# box_opener.net
KiCad netlist of a schematic drawn in EAGLE
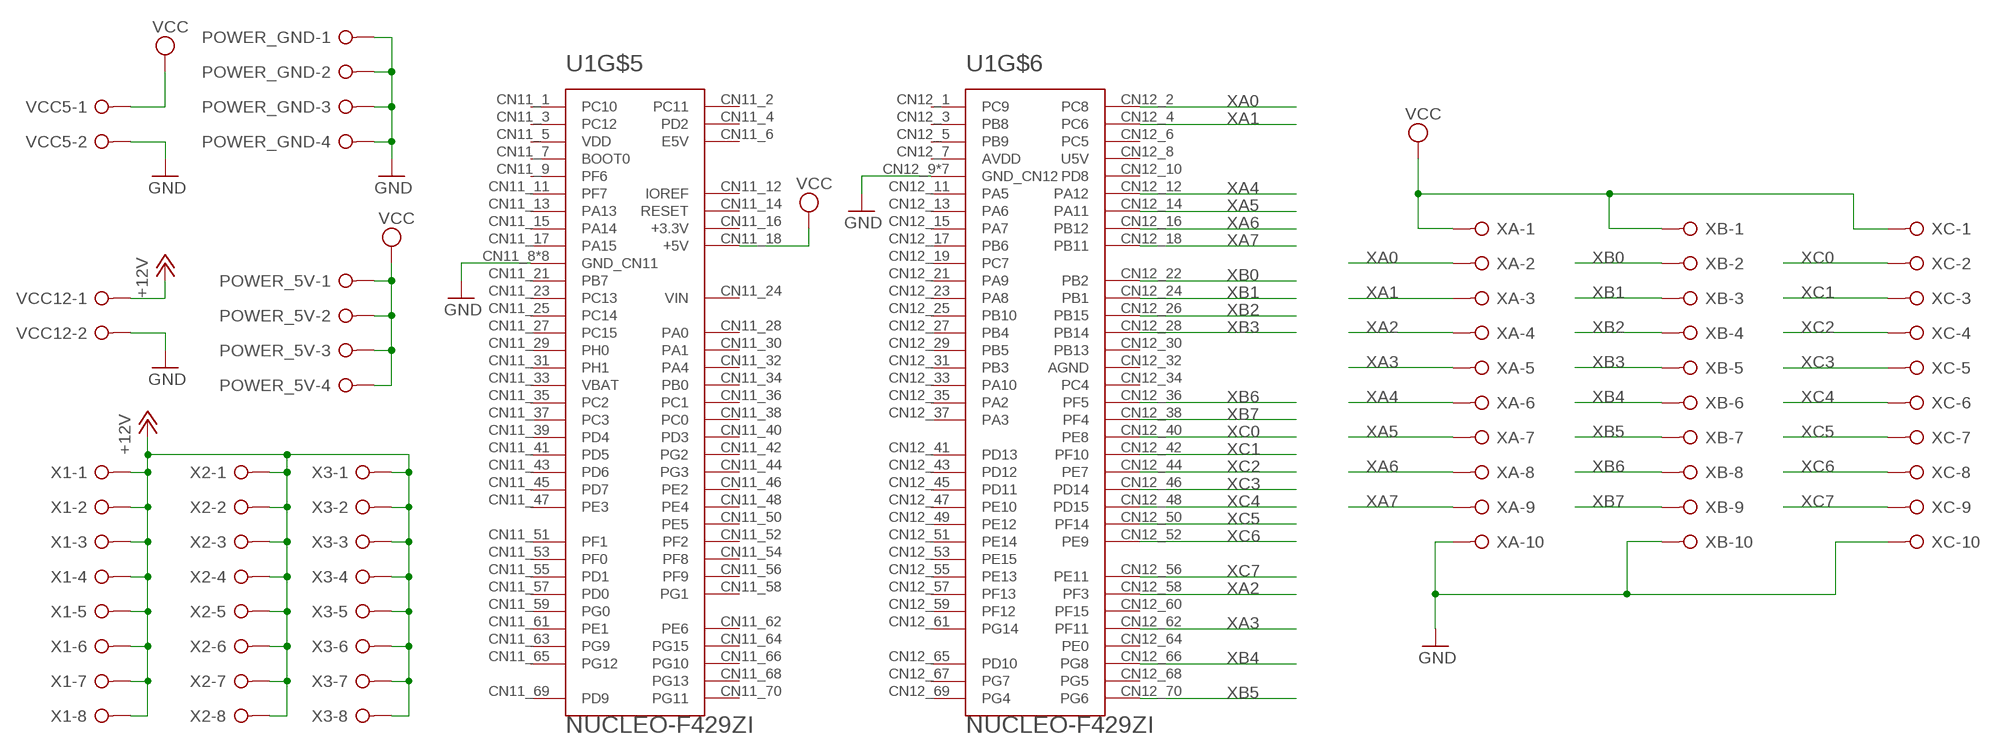
[diagram p0: schematic, sheet 1]

(export (version "E")
  (design (tool "Eeschema 10.0.6"))
  (components
    (comp (ref "POWER_5V")
      (value "W237-04P")
      (footprint "eagle-import:W237-4P")
      (libsource (lib "eagle-import") (part "W237-04P"))
    )
    (comp (ref "POWER_GND")
      (value "W237-04P")
      (footprint "eagle-import:W237-4P")
      (libsource (lib "eagle-import") (part "W237-04P"))
    )
    (comp (ref "U1")
      (value "NUCLEO-F429ZI")
      (footprint "eagle-import:MODULE_NUCLEO-F429ZI")
      (fields (field (name "MF") "STMicroelectronics"))
      (libsource (lib "eagle-import") (part "NUCLEO-F429ZI"))
    )
    (comp (ref "VCC5")
      (value "W237-02P")
      (footprint "eagle-import:W237-132")
      (libsource (lib "eagle-import") (part "W237-02P"))
    )
    (comp (ref "VCC12")
      (value "W237-02P")
      (footprint "eagle-import:W237-132")
      (libsource (lib "eagle-import") (part "W237-02P"))
    )
    (comp (ref "X1")
      (value "W237-08P")
      (footprint "eagle-import:W237-8P")
      (libsource (lib "eagle-import") (part "W237-08P"))
    )
    (comp (ref "X2")
      (value "W237-08P")
      (footprint "eagle-import:W237-8P")
      (libsource (lib "eagle-import") (part "W237-08P"))
    )
    (comp (ref "X3")
      (value "W237-08P")
      (footprint "eagle-import:W237-8P")
      (libsource (lib "eagle-import") (part "W237-08P"))
    )
    (comp (ref "XA")
      (value "W237-10P")
      (footprint "eagle-import:W237-10P")
      (libsource (lib "eagle-import") (part "W237-10P"))
    )
    (comp (ref "XB")
      (value "W237-10P")
      (footprint "eagle-import:W237-10P")
      (libsource (lib "eagle-import") (part "W237-10P"))
    )
    (comp (ref "XC")
      (value "W237-10P")
      (footprint "eagle-import:W237-10P")
      (libsource (lib "eagle-import") (part "W237-10P"))
    )
  )
  (nets
    (net (code "1") (name "+12V") (class "Default")
      (node (ref "VCC12") (pin "1") (pinfunction "KL_1") (pintype "passive"))
      (node (ref "X1") (pin "1") (pinfunction "KL_1") (pintype "passive"))
      (node (ref "X1") (pin "2") (pinfunction "KL_2") (pintype "passive"))
      (node (ref "X1") (pin "3") (pinfunction "KL_3") (pintype "passive"))
      (node (ref "X1") (pin "4") (pinfunction "KL_4") (pintype "passive"))
      (node (ref "X1") (pin "5") (pinfunction "KL_5") (pintype "passive"))
      (node (ref "X1") (pin "6") (pinfunction "KL_6") (pintype "passive"))
      (node (ref "X1") (pin "7") (pinfunction "KL_7") (pintype "passive"))
      (node (ref "X1") (pin "8") (pinfunction "KL_8") (pintype "passive"))
      (node (ref "X2") (pin "1") (pinfunction "KL_1") (pintype "passive"))
      (node (ref "X2") (pin "2") (pinfunction "KL_2") (pintype "passive"))
      (node (ref "X2") (pin "3") (pinfunction "KL_3") (pintype "passive"))
      (node (ref "X2") (pin "4") (pinfunction "KL_4") (pintype "passive"))
      (node (ref "X2") (pin "5") (pinfunction "KL_5") (pintype "passive"))
      (node (ref "X2") (pin "6") (pinfunction "KL_6") (pintype "passive"))
      (node (ref "X2") (pin "7") (pinfunction "KL_7") (pintype "passive"))
      (node (ref "X2") (pin "8") (pinfunction "KL_8") (pintype "passive"))
      (node (ref "X3") (pin "1") (pinfunction "KL_1") (pintype "passive"))
      (node (ref "X3") (pin "2") (pinfunction "KL_2") (pintype "passive"))
      (node (ref "X3") (pin "3") (pinfunction "KL_3") (pintype "passive"))
      (node (ref "X3") (pin "4") (pinfunction "KL_4") (pintype "passive"))
      (node (ref "X3") (pin "5") (pinfunction "KL_5") (pintype "passive"))
      (node (ref "X3") (pin "6") (pinfunction "KL_6") (pintype "passive"))
      (node (ref "X3") (pin "7") (pinfunction "KL_7") (pintype "passive"))
      (node (ref "X3") (pin "8") (pinfunction "KL_8") (pintype "passive"))
    )
    (net (code "2") (name "/XA0") (class "Default")
      (node (ref "U1") (pin "CN12_2") (pinfunction "PC8_CN12_2") (pintype "passive"))
      (node (ref "XA") (pin "2") (pinfunction "KL_2") (pintype "passive"))
    )
    (net (code "3") (name "/XA1") (class "Default")
      (node (ref "U1") (pin "CN12_4") (pinfunction "PC6_CN12_4") (pintype "passive"))
      (node (ref "XA") (pin "3") (pinfunction "KL_3") (pintype "passive"))
    )
    (net (code "4") (name "/XA2") (class "Default")
      (node (ref "U1") (pin "CN12_58") (pinfunction "PF3_CN12_58") (pintype "passive"))
      (node (ref "XA") (pin "4") (pinfunction "KL_4") (pintype "passive"))
    )
    (net (code "5") (name "/XA3") (class "Default")
      (node (ref "U1") (pin "CN12_62") (pinfunction "PF11_CN12_62") (pintype "passive"))
      (node (ref "XA") (pin "5") (pinfunction "KL_5") (pintype "passive"))
    )
    (net (code "6") (name "/XA4") (class "Default")
      (node (ref "U1") (pin "CN12_12") (pinfunction "PA12_CN12_12") (pintype "passive"))
      (node (ref "XA") (pin "6") (pinfunction "KL_6") (pintype "passive"))
    )
    (net (code "7") (name "/XA5") (class "Default")
      (node (ref "U1") (pin "CN12_14") (pinfunction "PA11_CN12_14") (pintype "passive"))
      (node (ref "XA") (pin "7") (pinfunction "KL_7") (pintype "passive"))
    )
    (net (code "8") (name "/XA6") (class "Default")
      (node (ref "U1") (pin "CN12_16") (pinfunction "PB12_CN12_16") (pintype "passive"))
      (node (ref "XA") (pin "8") (pinfunction "KL_8") (pintype "passive"))
    )
    (net (code "9") (name "/XA7") (class "Default")
      (node (ref "U1") (pin "CN12_18") (pinfunction "PB11_CN12_18") (pintype "passive"))
      (node (ref "XA") (pin "9") (pinfunction "KL_9") (pintype "passive"))
    )
    (net (code "10") (name "/XB0") (class "Default")
      (node (ref "U1") (pin "CN12_22") (pinfunction "PB2_CN12_22") (pintype "passive"))
      (node (ref "XB") (pin "2") (pinfunction "KL_2") (pintype "passive"))
    )
    (net (code "11") (name "/XB1") (class "Default")
      (node (ref "U1") (pin "CN12_24") (pinfunction "PB1_CN12_24") (pintype "passive"))
      (node (ref "XB") (pin "3") (pinfunction "KL_3") (pintype "passive"))
    )
    (net (code "12") (name "/XB2") (class "Default")
      (node (ref "U1") (pin "CN12_26") (pinfunction "PB15_CN12_26") (pintype "passive"))
      (node (ref "XB") (pin "4") (pinfunction "KL_4") (pintype "passive"))
    )
    (net (code "13") (name "/XB3") (class "Default")
      (node (ref "U1") (pin "CN12_28") (pinfunction "PB14_CN12_28") (pintype "passive"))
      (node (ref "XB") (pin "5") (pinfunction "KL_5") (pintype "passive"))
    )
    (net (code "14") (name "/XB4") (class "Default")
      (node (ref "U1") (pin "CN12_66") (pinfunction "PG8_CN12_66") (pintype "passive"))
      (node (ref "XB") (pin "6") (pinfunction "KL_6") (pintype "passive"))
    )
    (net (code "15") (name "/XB5") (class "Default")
      (node (ref "U1") (pin "CN12_70") (pinfunction "PG6_CN12_70") (pintype "passive"))
      (node (ref "XB") (pin "7") (pinfunction "KL_7") (pintype "passive"))
    )
    (net (code "16") (name "/XB6") (class "Default")
      (node (ref "U1") (pin "CN12_36") (pinfunction "PF5_CN12_36") (pintype "passive"))
      (node (ref "XB") (pin "8") (pinfunction "KL_8") (pintype "passive"))
    )
    (net (code "17") (name "/XB7") (class "Default")
      (node (ref "U1") (pin "CN12_38") (pinfunction "PF4_CN12_38") (pintype "passive"))
      (node (ref "XB") (pin "9") (pinfunction "KL_9") (pintype "passive"))
    )
    (net (code "18") (name "/XC0") (class "Default")
      (node (ref "U1") (pin "CN12_40") (pinfunction "PE8_CN12_40") (pintype "passive"))
      (node (ref "XC") (pin "2") (pinfunction "KL_2") (pintype "passive"))
    )
    (net (code "19") (name "/XC1") (class "Default")
      (node (ref "U1") (pin "CN12_42") (pinfunction "PF10_CN12_42") (pintype "passive"))
      (node (ref "XC") (pin "3") (pinfunction "KL_3") (pintype "passive"))
    )
    (net (code "20") (name "/XC2") (class "Default")
      (node (ref "U1") (pin "CN12_44") (pinfunction "PE7_CN12_44") (pintype "passive"))
      (node (ref "XC") (pin "4") (pinfunction "KL_4") (pintype "passive"))
    )
    (net (code "21") (name "/XC3") (class "Default")
      (node (ref "U1") (pin "CN12_46") (pinfunction "PD14_CN12_46") (pintype "passive"))
      (node (ref "XC") (pin "5") (pinfunction "KL_5") (pintype "passive"))
    )
    (net (code "22") (name "/XC4") (class "Default")
      (node (ref "U1") (pin "CN12_48") (pinfunction "PD15_CN12_48") (pintype "passive"))
      (node (ref "XC") (pin "6") (pinfunction "KL_6") (pintype "passive"))
    )
    (net (code "23") (name "/XC5") (class "Default")
      (node (ref "U1") (pin "CN12_50") (pinfunction "PF14_CN12_50") (pintype "passive"))
      (node (ref "XC") (pin "7") (pinfunction "KL_7") (pintype "passive"))
    )
    (net (code "24") (name "/XC6") (class "Default")
      (node (ref "U1") (pin "CN12_52") (pinfunction "PE9_CN12_52") (pintype "passive"))
      (node (ref "XC") (pin "8") (pinfunction "KL_8") (pintype "passive"))
    )
    (net (code "25") (name "/XC7") (class "Default")
      (node (ref "U1") (pin "CN12_56") (pinfunction "PE11_CN12_56") (pintype "passive"))
      (node (ref "XC") (pin "9") (pinfunction "KL_9") (pintype "passive"))
    )
    (net (code "26") (name "GND") (class "Default")
      (node (ref "POWER_GND") (pin "1") (pinfunction "KL_1") (pintype "passive"))
      (node (ref "POWER_GND") (pin "2") (pinfunction "KL_2") (pintype "passive"))
      (node (ref "POWER_GND") (pin "3") (pinfunction "KL_3") (pintype "passive"))
      (node (ref "POWER_GND") (pin "4") (pinfunction "KL_4") (pintype "passive"))
      (node (ref "U1") (pin "CN11_19") (pinfunction "GND_CN11_CN11_19") (pintype "passive"))
      (node (ref "U1") (pin "CN11_20") (pinfunction "GND_CN11_CN11_20") (pintype "passive"))
      (node (ref "U1") (pin "CN11_22") (pinfunction "GND_CN11_CN11_22") (pintype "passive"))
      (node (ref "U1") (pin "CN11_49") (pinfunction "GND_CN11_CN11_49") (pintype "passive"))
      (node (ref "U1") (pin "CN11_60") (pinfunction "GND_CN11_CN11_60") (pintype "passive"))
      (node (ref "U1") (pin "CN11_71") (pinfunction "GND_CN11_CN11_71") (pintype "passive"))
      (node (ref "U1") (pin "CN11_72") (pinfunction "GND_CN11_CN11_72") (pintype "passive"))
      (node (ref "U1") (pin "CN11_8") (pinfunction "GND_CN11_CN11_8") (pintype "passive"))
      (node (ref "U1") (pin "CN12_20") (pinfunction "GND_CN12_CN12_20") (pintype "passive"))
      (node (ref "U1") (pin "CN12_39") (pinfunction "GND_CN12_CN12_39") (pintype "passive"))
      (node (ref "U1") (pin "CN12_54") (pinfunction "GND_CN12_CN12_54") (pintype "passive"))
      (node (ref "U1") (pin "CN12_63") (pinfunction "GND_CN12_CN12_63") (pintype "passive"))
      (node (ref "U1") (pin "CN12_71") (pinfunction "GND_CN12_CN12_71") (pintype "passive"))
      (node (ref "U1") (pin "CN12_72") (pinfunction "GND_CN12_CN12_72") (pintype "passive"))
      (node (ref "U1") (pin "CN12_9") (pinfunction "GND_CN12_CN12_9") (pintype "passive"))
      (node (ref "VCC12") (pin "2") (pinfunction "KL_2") (pintype "passive"))
      (node (ref "VCC5") (pin "2") (pinfunction "KL_2") (pintype "passive"))
      (node (ref "XA") (pin "10") (pinfunction "KL_10") (pintype "passive"))
      (node (ref "XB") (pin "10") (pinfunction "KL_10") (pintype "passive"))
      (node (ref "XC") (pin "10") (pinfunction "KL_10") (pintype "passive"))
    )
    (net (code "27") (name "VCC") (class "Default")
      (node (ref "POWER_5V") (pin "1") (pinfunction "KL_1") (pintype "passive"))
      (node (ref "POWER_5V") (pin "2") (pinfunction "KL_2") (pintype "passive"))
      (node (ref "POWER_5V") (pin "3") (pinfunction "KL_3") (pintype "passive"))
      (node (ref "POWER_5V") (pin "4") (pinfunction "KL_4") (pintype "passive"))
      (node (ref "U1") (pin "CN11_18") (pinfunction "+5V_CN11_18") (pintype "passive"))
      (node (ref "VCC5") (pin "1") (pinfunction "KL_1") (pintype "passive"))
      (node (ref "XA") (pin "1") (pinfunction "KL_1") (pintype "passive"))
      (node (ref "XB") (pin "1") (pinfunction "KL_1") (pintype "passive"))
      (node (ref "XC") (pin "1") (pinfunction "KL_1") (pintype "passive"))
    )
    (net (code "28") (name "unconnected-(U1E-+3.3V-PadCN11_16)") (class "Default")
      (node (ref "U1") (pin "CN11_16") (pinfunction "+3.3V_CN11_16") (pintype "passive"))
    )
    (net (code "29") (name "unconnected-(U1E-BOOT0-PadCN11_7)") (class "Default")
      (node (ref "U1") (pin "CN11_7") (pinfunction "BOOT0_CN11_7") (pintype "passive"))
    )
    (net (code "30") (name "unconnected-(U1E-E5V-PadCN11_6)") (class "Default")
      (node (ref "U1") (pin "CN11_6") (pinfunction "E5V_CN11_6") (pintype "passive"))
    )
    (net (code "31") (name "unconnected-(U1E-IOREF-PadCN11_12)") (class "Default")
      (node (ref "U1") (pin "CN11_12") (pinfunction "IOREF_CN11_12") (pintype "passive"))
    )
    (net (code "32") (name "unconnected-(U1E-PA0-PadCN11_28)") (class "Default")
      (node (ref "U1") (pin "CN11_28") (pinfunction "PA0_CN11_28") (pintype "passive"))
    )
    (net (code "33") (name "unconnected-(U1E-PA1-PadCN11_30)") (class "Default")
      (node (ref "U1") (pin "CN11_30") (pinfunction "PA1_CN11_30") (pintype "passive"))
    )
    (net (code "34") (name "unconnected-(U1E-PA4-PadCN11_32)") (class "Default")
      (node (ref "U1") (pin "CN11_32") (pinfunction "PA4_CN11_32") (pintype "passive"))
    )
    (net (code "35") (name "unconnected-(U1E-PA13-PadCN11_13)") (class "Default")
      (node (ref "U1") (pin "CN11_13") (pinfunction "PA13_CN11_13") (pintype "passive"))
    )
    (net (code "36") (name "unconnected-(U1E-PA14-PadCN11_15)") (class "Default")
      (node (ref "U1") (pin "CN11_15") (pinfunction "PA14_CN11_15") (pintype "passive"))
    )
    (net (code "37") (name "unconnected-(U1E-PA15-PadCN11_17)") (class "Default")
      (node (ref "U1") (pin "CN11_17") (pinfunction "PA15_CN11_17") (pintype "passive"))
    )
    (net (code "38") (name "unconnected-(U1E-PB0-PadCN11_34)") (class "Default")
      (node (ref "U1") (pin "CN11_34") (pinfunction "PB0_CN11_34") (pintype "passive"))
    )
    (net (code "39") (name "unconnected-(U1E-PB7-PadCN11_21)") (class "Default")
      (node (ref "U1") (pin "CN11_21") (pinfunction "PB7_CN11_21") (pintype "passive"))
    )
    (net (code "40") (name "unconnected-(U1E-PC0-PadCN11_38)") (class "Default")
      (node (ref "U1") (pin "CN11_38") (pinfunction "PC0_CN11_38") (pintype "passive"))
    )
    (net (code "41") (name "unconnected-(U1E-PC1-PadCN11_36)") (class "Default")
      (node (ref "U1") (pin "CN11_36") (pinfunction "PC1_CN11_36") (pintype "passive"))
    )
    (net (code "42") (name "unconnected-(U1E-PC2-PadCN11_35)") (class "Default")
      (node (ref "U1") (pin "CN11_35") (pinfunction "PC2_CN11_35") (pintype "passive"))
    )
    (net (code "43") (name "unconnected-(U1E-PC3-PadCN11_37)") (class "Default")
      (node (ref "U1") (pin "CN11_37") (pinfunction "PC3_CN11_37") (pintype "passive"))
    )
    (net (code "44") (name "unconnected-(U1E-PC10-PadCN11_1)") (class "Default")
      (node (ref "U1") (pin "CN11_1") (pinfunction "PC10_CN11_1") (pintype "passive"))
    )
    (net (code "45") (name "unconnected-(U1E-PC11-PadCN11_2)") (class "Default")
      (node (ref "U1") (pin "CN11_2") (pinfunction "PC11_CN11_2") (pintype "passive"))
    )
    (net (code "46") (name "unconnected-(U1E-PC12-PadCN11_3)") (class "Default")
      (node (ref "U1") (pin "CN11_3") (pinfunction "PC12_CN11_3") (pintype "passive"))
    )
    (net (code "47") (name "unconnected-(U1E-PC13-PadCN11_23)") (class "Default")
      (node (ref "U1") (pin "CN11_23") (pinfunction "PC13_CN11_23") (pintype "passive"))
    )
    (net (code "48") (name "unconnected-(U1E-PC14-PadCN11_25)") (class "Default")
      (node (ref "U1") (pin "CN11_25") (pinfunction "PC14_CN11_25") (pintype "passive"))
    )
    (net (code "49") (name "unconnected-(U1E-PC15-PadCN11_27)") (class "Default")
      (node (ref "U1") (pin "CN11_27") (pinfunction "PC15_CN11_27") (pintype "passive"))
    )
    (net (code "50") (name "unconnected-(U1E-PD0-PadCN11_57)") (class "Default")
      (node (ref "U1") (pin "CN11_57") (pinfunction "PD0_CN11_57") (pintype "passive"))
    )
    (net (code "51") (name "unconnected-(U1E-PD1-PadCN11_55)") (class "Default")
      (node (ref "U1") (pin "CN11_55") (pinfunction "PD1_CN11_55") (pintype "passive"))
    )
    (net (code "52") (name "unconnected-(U1E-PD2-PadCN11_4)") (class "Default")
      (node (ref "U1") (pin "CN11_4") (pinfunction "PD2_CN11_4") (pintype "passive"))
    )
    (net (code "53") (name "unconnected-(U1E-PD3-PadCN11_40)") (class "Default")
      (node (ref "U1") (pin "CN11_40") (pinfunction "PD3_CN11_40") (pintype "passive"))
    )
    (net (code "54") (name "unconnected-(U1E-PD4-PadCN11_39)") (class "Default")
      (node (ref "U1") (pin "CN11_39") (pinfunction "PD4_CN11_39") (pintype "passive"))
    )
    (net (code "55") (name "unconnected-(U1E-PD5-PadCN11_41)") (class "Default")
      (node (ref "U1") (pin "CN11_41") (pinfunction "PD5_CN11_41") (pintype "passive"))
    )
    (net (code "56") (name "unconnected-(U1E-PD6-PadCN11_43)") (class "Default")
      (node (ref "U1") (pin "CN11_43") (pinfunction "PD6_CN11_43") (pintype "passive"))
    )
    (net (code "57") (name "unconnected-(U1E-PD7-PadCN11_45)") (class "Default")
      (node (ref "U1") (pin "CN11_45") (pinfunction "PD7_CN11_45") (pintype "passive"))
    )
    (net (code "58") (name "unconnected-(U1E-PD9-PadCN11_69)") (class "Default")
      (node (ref "U1") (pin "CN11_69") (pinfunction "PD9_CN11_69") (pintype "passive"))
    )
    (net (code "59") (name "unconnected-(U1E-PE1-PadCN11_61)") (class "Default")
      (node (ref "U1") (pin "CN11_61") (pinfunction "PE1_CN11_61") (pintype "passive"))
    )
    (net (code "60") (name "unconnected-(U1E-PE2-PadCN11_46)") (class "Default")
      (node (ref "U1") (pin "CN11_46") (pinfunction "PE2_CN11_46") (pintype "passive"))
    )
    (net (code "61") (name "unconnected-(U1E-PE3-PadCN11_47)") (class "Default")
      (node (ref "U1") (pin "CN11_47") (pinfunction "PE3_CN11_47") (pintype "passive"))
    )
    (net (code "62") (name "unconnected-(U1E-PE4-PadCN11_48)") (class "Default")
      (node (ref "U1") (pin "CN11_48") (pinfunction "PE4_CN11_48") (pintype "passive"))
    )
    (net (code "63") (name "unconnected-(U1E-PE5-PadCN11_50)") (class "Default")
      (node (ref "U1") (pin "CN11_50") (pinfunction "PE5_CN11_50") (pintype "passive"))
    )
    (net (code "64") (name "unconnected-(U1E-PE6-PadCN11_62)") (class "Default")
      (node (ref "U1") (pin "CN11_62") (pinfunction "PE6_CN11_62") (pintype "passive"))
    )
    (net (code "65") (name "unconnected-(U1E-PF0-PadCN11_53)") (class "Default")
      (node (ref "U1") (pin "CN11_53") (pinfunction "PF0_CN11_53") (pintype "passive"))
    )
    (net (code "66") (name "unconnected-(U1E-PF1-PadCN11_51)") (class "Default")
      (node (ref "U1") (pin "CN11_51") (pinfunction "PF1_CN11_51") (pintype "passive"))
    )
    (net (code "67") (name "unconnected-(U1E-PF2-PadCN11_52)") (class "Default")
      (node (ref "U1") (pin "CN11_52") (pinfunction "PF2_CN11_52") (pintype "passive"))
    )
    (net (code "68") (name "unconnected-(U1E-PF6-PadCN11_9)") (class "Default")
      (node (ref "U1") (pin "CN11_9") (pinfunction "PF6_CN11_9") (pintype "passive"))
    )
    (net (code "69") (name "unconnected-(U1E-PF7-PadCN11_11)") (class "Default")
      (node (ref "U1") (pin "CN11_11") (pinfunction "PF7_CN11_11") (pintype "passive"))
    )
    (net (code "70") (name "unconnected-(U1E-PF8-PadCN11_54)") (class "Default")
      (node (ref "U1") (pin "CN11_54") (pinfunction "PF8_CN11_54") (pintype "passive"))
    )
    (net (code "71") (name "unconnected-(U1E-PF9-PadCN11_56)") (class "Default")
      (node (ref "U1") (pin "CN11_56") (pinfunction "PF9_CN11_56") (pintype "passive"))
    )
    (net (code "72") (name "unconnected-(U1E-PG0-PadCN11_59)") (class "Default")
      (node (ref "U1") (pin "CN11_59") (pinfunction "PG0_CN11_59") (pintype "passive"))
    )
    (net (code "73") (name "unconnected-(U1E-PG1-PadCN11_58)") (class "Default")
      (node (ref "U1") (pin "CN11_58") (pinfunction "PG1_CN11_58") (pintype "passive"))
    )
    (net (code "74") (name "unconnected-(U1E-PG2-PadCN11_42)") (class "Default")
      (node (ref "U1") (pin "CN11_42") (pinfunction "PG2_CN11_42") (pintype "passive"))
    )
    (net (code "75") (name "unconnected-(U1E-PG3-PadCN11_44)") (class "Default")
      (node (ref "U1") (pin "CN11_44") (pinfunction "PG3_CN11_44") (pintype "passive"))
    )
    (net (code "76") (name "unconnected-(U1E-PG9-PadCN11_63)") (class "Default")
      (node (ref "U1") (pin "CN11_63") (pinfunction "PG9_CN11_63") (pintype "passive"))
    )
    (net (code "77") (name "unconnected-(U1E-PG10-PadCN11_66)") (class "Default")
      (node (ref "U1") (pin "CN11_66") (pinfunction "PG10_CN11_66") (pintype "passive"))
    )
    (net (code "78") (name "unconnected-(U1E-PG11-PadCN11_70)") (class "Default")
      (node (ref "U1") (pin "CN11_70") (pinfunction "PG11_CN11_70") (pintype "passive"))
    )
    (net (code "79") (name "unconnected-(U1E-PG12-PadCN11_65)") (class "Default")
      (node (ref "U1") (pin "CN11_65") (pinfunction "PG12_CN11_65") (pintype "passive"))
    )
    (net (code "80") (name "unconnected-(U1E-PG13-PadCN11_68)") (class "Default")
      (node (ref "U1") (pin "CN11_68") (pinfunction "PG13_CN11_68") (pintype "passive"))
    )
    (net (code "81") (name "unconnected-(U1E-PG15-PadCN11_64)") (class "Default")
      (node (ref "U1") (pin "CN11_64") (pinfunction "PG15_CN11_64") (pintype "passive"))
    )
    (net (code "82") (name "unconnected-(U1E-PH0-PadCN11_29)") (class "Default")
      (node (ref "U1") (pin "CN11_29") (pinfunction "PH0_CN11_29") (pintype "passive"))
    )
    (net (code "83") (name "unconnected-(U1E-PH1-PadCN11_31)") (class "Default")
      (node (ref "U1") (pin "CN11_31") (pinfunction "PH1_CN11_31") (pintype "passive"))
    )
    (net (code "84") (name "unconnected-(U1E-RESET-PadCN11_14)") (class "Default")
      (node (ref "U1") (pin "CN11_14") (pinfunction "RESET_CN11_14") (pintype "passive"))
    )
    (net (code "85") (name "unconnected-(U1E-VBAT-PadCN11_33)") (class "Default")
      (node (ref "U1") (pin "CN11_33") (pinfunction "VBAT_CN11_33") (pintype "passive"))
    )
    (net (code "86") (name "unconnected-(U1E-VDD-PadCN11_5)") (class "Default")
      (node (ref "U1") (pin "CN11_5") (pinfunction "VDD_CN11_5") (pintype "passive"))
    )
    (net (code "87") (name "unconnected-(U1E-VIN-PadCN11_24)") (class "Default")
      (node (ref "U1") (pin "CN11_24") (pinfunction "VIN_CN11_24") (pintype "passive"))
    )
    (net (code "88") (name "unconnected-(U1F-AGND-PadCN12_32)") (class "Default")
      (node (ref "U1") (pin "CN12_32") (pinfunction "AGND_CN12_32") (pintype "passive"))
    )
    (net (code "89") (name "unconnected-(U1F-AVDD-PadCN12_7)") (class "Default")
      (node (ref "U1") (pin "CN12_7") (pinfunction "AVDD_CN12_7") (pintype "passive"))
    )
    (net (code "90") (name "unconnected-(U1F-PA2-PadCN12_35)") (class "Default")
      (node (ref "U1") (pin "CN12_35") (pinfunction "PA2_CN12_35") (pintype "passive"))
    )
    (net (code "91") (name "unconnected-(U1F-PA3-PadCN12_37)") (class "Default")
      (node (ref "U1") (pin "CN12_37") (pinfunction "PA3_CN12_37") (pintype "passive"))
    )
    (net (code "92") (name "unconnected-(U1F-PA5-PadCN12_11)") (class "Default")
      (node (ref "U1") (pin "CN12_11") (pinfunction "PA5_CN12_11") (pintype "passive"))
    )
    (net (code "93") (name "unconnected-(U1F-PA6-PadCN12_13)") (class "Default")
      (node (ref "U1") (pin "CN12_13") (pinfunction "PA6_CN12_13") (pintype "passive"))
    )
    (net (code "94") (name "unconnected-(U1F-PA7-PadCN12_15)") (class "Default")
      (node (ref "U1") (pin "CN12_15") (pinfunction "PA7_CN12_15") (pintype "passive"))
    )
    (net (code "95") (name "unconnected-(U1F-PA8-PadCN12_23)") (class "Default")
      (node (ref "U1") (pin "CN12_23") (pinfunction "PA8_CN12_23") (pintype "passive"))
    )
    (net (code "96") (name "unconnected-(U1F-PA9-PadCN12_21)") (class "Default")
      (node (ref "U1") (pin "CN12_21") (pinfunction "PA9_CN12_21") (pintype "passive"))
    )
    (net (code "97") (name "unconnected-(U1F-PA10-PadCN12_33)") (class "Default")
      (node (ref "U1") (pin "CN12_33") (pinfunction "PA10_CN12_33") (pintype "passive"))
    )
    (net (code "98") (name "unconnected-(U1F-PB3-PadCN12_31)") (class "Default")
      (node (ref "U1") (pin "CN12_31") (pinfunction "PB3_CN12_31") (pintype "passive"))
    )
    (net (code "99") (name "unconnected-(U1F-PB4-PadCN12_27)") (class "Default")
      (node (ref "U1") (pin "CN12_27") (pinfunction "PB4_CN12_27") (pintype "passive"))
    )
    (net (code "100") (name "unconnected-(U1F-PB5-PadCN12_29)") (class "Default")
      (node (ref "U1") (pin "CN12_29") (pinfunction "PB5_CN12_29") (pintype "passive"))
    )
    (net (code "101") (name "unconnected-(U1F-PB6-PadCN12_17)") (class "Default")
      (node (ref "U1") (pin "CN12_17") (pinfunction "PB6_CN12_17") (pintype "passive"))
    )
    (net (code "102") (name "unconnected-(U1F-PB8-PadCN12_3)") (class "Default")
      (node (ref "U1") (pin "CN12_3") (pinfunction "PB8_CN12_3") (pintype "passive"))
    )
    (net (code "103") (name "unconnected-(U1F-PB9-PadCN12_5)") (class "Default")
      (node (ref "U1") (pin "CN12_5") (pinfunction "PB9_CN12_5") (pintype "passive"))
    )
    (net (code "104") (name "unconnected-(U1F-PB10-PadCN12_25)") (class "Default")
      (node (ref "U1") (pin "CN12_25") (pinfunction "PB10_CN12_25") (pintype "passive"))
    )
    (net (code "105") (name "unconnected-(U1F-PB13-PadCN12_30)") (class "Default")
      (node (ref "U1") (pin "CN12_30") (pinfunction "PB13_CN12_30") (pintype "passive"))
    )
    (net (code "106") (name "unconnected-(U1F-PC4-PadCN12_34)") (class "Default")
      (node (ref "U1") (pin "CN12_34") (pinfunction "PC4_CN12_34") (pintype "passive"))
    )
    (net (code "107") (name "unconnected-(U1F-PC5-PadCN12_6)") (class "Default")
      (node (ref "U1") (pin "CN12_6") (pinfunction "PC5_CN12_6") (pintype "passive"))
    )
    (net (code "108") (name "unconnected-(U1F-PC7-PadCN12_19)") (class "Default")
      (node (ref "U1") (pin "CN12_19") (pinfunction "PC7_CN12_19") (pintype "passive"))
    )
    (net (code "109") (name "unconnected-(U1F-PC9-PadCN12_1)") (class "Default")
      (node (ref "U1") (pin "CN12_1") (pinfunction "PC9_CN12_1") (pintype "passive"))
    )
    (net (code "110") (name "unconnected-(U1F-PD8-PadCN12_10)") (class "Default")
      (node (ref "U1") (pin "CN12_10") (pinfunction "PD8_CN12_10") (pintype "passive"))
    )
    (net (code "111") (name "unconnected-(U1F-PD10-PadCN12_65)") (class "Default")
      (node (ref "U1") (pin "CN12_65") (pinfunction "PD10_CN12_65") (pintype "passive"))
    )
    (net (code "112") (name "unconnected-(U1F-PD11-PadCN12_45)") (class "Default")
      (node (ref "U1") (pin "CN12_45") (pinfunction "PD11_CN12_45") (pintype "passive"))
    )
    (net (code "113") (name "unconnected-(U1F-PD12-PadCN12_43)") (class "Default")
      (node (ref "U1") (pin "CN12_43") (pinfunction "PD12_CN12_43") (pintype "passive"))
    )
    (net (code "114") (name "unconnected-(U1F-PD13-PadCN12_41)") (class "Default")
      (node (ref "U1") (pin "CN12_41") (pinfunction "PD13_CN12_41") (pintype "passive"))
    )
    (net (code "115") (name "unconnected-(U1F-PE0-PadCN12_64)") (class "Default")
      (node (ref "U1") (pin "CN12_64") (pinfunction "PE0_CN12_64") (pintype "passive"))
    )
    (net (code "116") (name "unconnected-(U1F-PE10-PadCN12_47)") (class "Default")
      (node (ref "U1") (pin "CN12_47") (pinfunction "PE10_CN12_47") (pintype "passive"))
    )
    (net (code "117") (name "unconnected-(U1F-PE12-PadCN12_49)") (class "Default")
      (node (ref "U1") (pin "CN12_49") (pinfunction "PE12_CN12_49") (pintype "passive"))
    )
    (net (code "118") (name "unconnected-(U1F-PE13-PadCN12_55)") (class "Default")
      (node (ref "U1") (pin "CN12_55") (pinfunction "PE13_CN12_55") (pintype "passive"))
    )
    (net (code "119") (name "unconnected-(U1F-PE14-PadCN12_51)") (class "Default")
      (node (ref "U1") (pin "CN12_51") (pinfunction "PE14_CN12_51") (pintype "passive"))
    )
    (net (code "120") (name "unconnected-(U1F-PE15-PadCN12_53)") (class "Default")
      (node (ref "U1") (pin "CN12_53") (pinfunction "PE15_CN12_53") (pintype "passive"))
    )
    (net (code "121") (name "unconnected-(U1F-PF12-PadCN12_59)") (class "Default")
      (node (ref "U1") (pin "CN12_59") (pinfunction "PF12_CN12_59") (pintype "passive"))
    )
    (net (code "122") (name "unconnected-(U1F-PF13-PadCN12_57)") (class "Default")
      (node (ref "U1") (pin "CN12_57") (pinfunction "PF13_CN12_57") (pintype "passive"))
    )
    (net (code "123") (name "unconnected-(U1F-PF15-PadCN12_60)") (class "Default")
      (node (ref "U1") (pin "CN12_60") (pinfunction "PF15_CN12_60") (pintype "passive"))
    )
    (net (code "124") (name "unconnected-(U1F-PG4-PadCN12_69)") (class "Default")
      (node (ref "U1") (pin "CN12_69") (pinfunction "PG4_CN12_69") (pintype "passive"))
    )
    (net (code "125") (name "unconnected-(U1F-PG5-PadCN12_68)") (class "Default")
      (node (ref "U1") (pin "CN12_68") (pinfunction "PG5_CN12_68") (pintype "passive"))
    )
    (net (code "126") (name "unconnected-(U1F-PG7-PadCN12_67)") (class "Default")
      (node (ref "U1") (pin "CN12_67") (pinfunction "PG7_CN12_67") (pintype "passive"))
    )
    (net (code "127") (name "unconnected-(U1F-PG14-PadCN12_61)") (class "Default")
      (node (ref "U1") (pin "CN12_61") (pinfunction "PG14_CN12_61") (pintype "passive"))
    )
    (net (code "128") (name "unconnected-(U1F-U5V-PadCN12_8)") (class "Default")
      (node (ref "U1") (pin "CN12_8") (pinfunction "U5V_CN12_8") (pintype "passive"))
    )
  )
)
